# WM_TriacSwitchModuleRev4.net
KiCad netlist of a schematic drawn in EAGLE
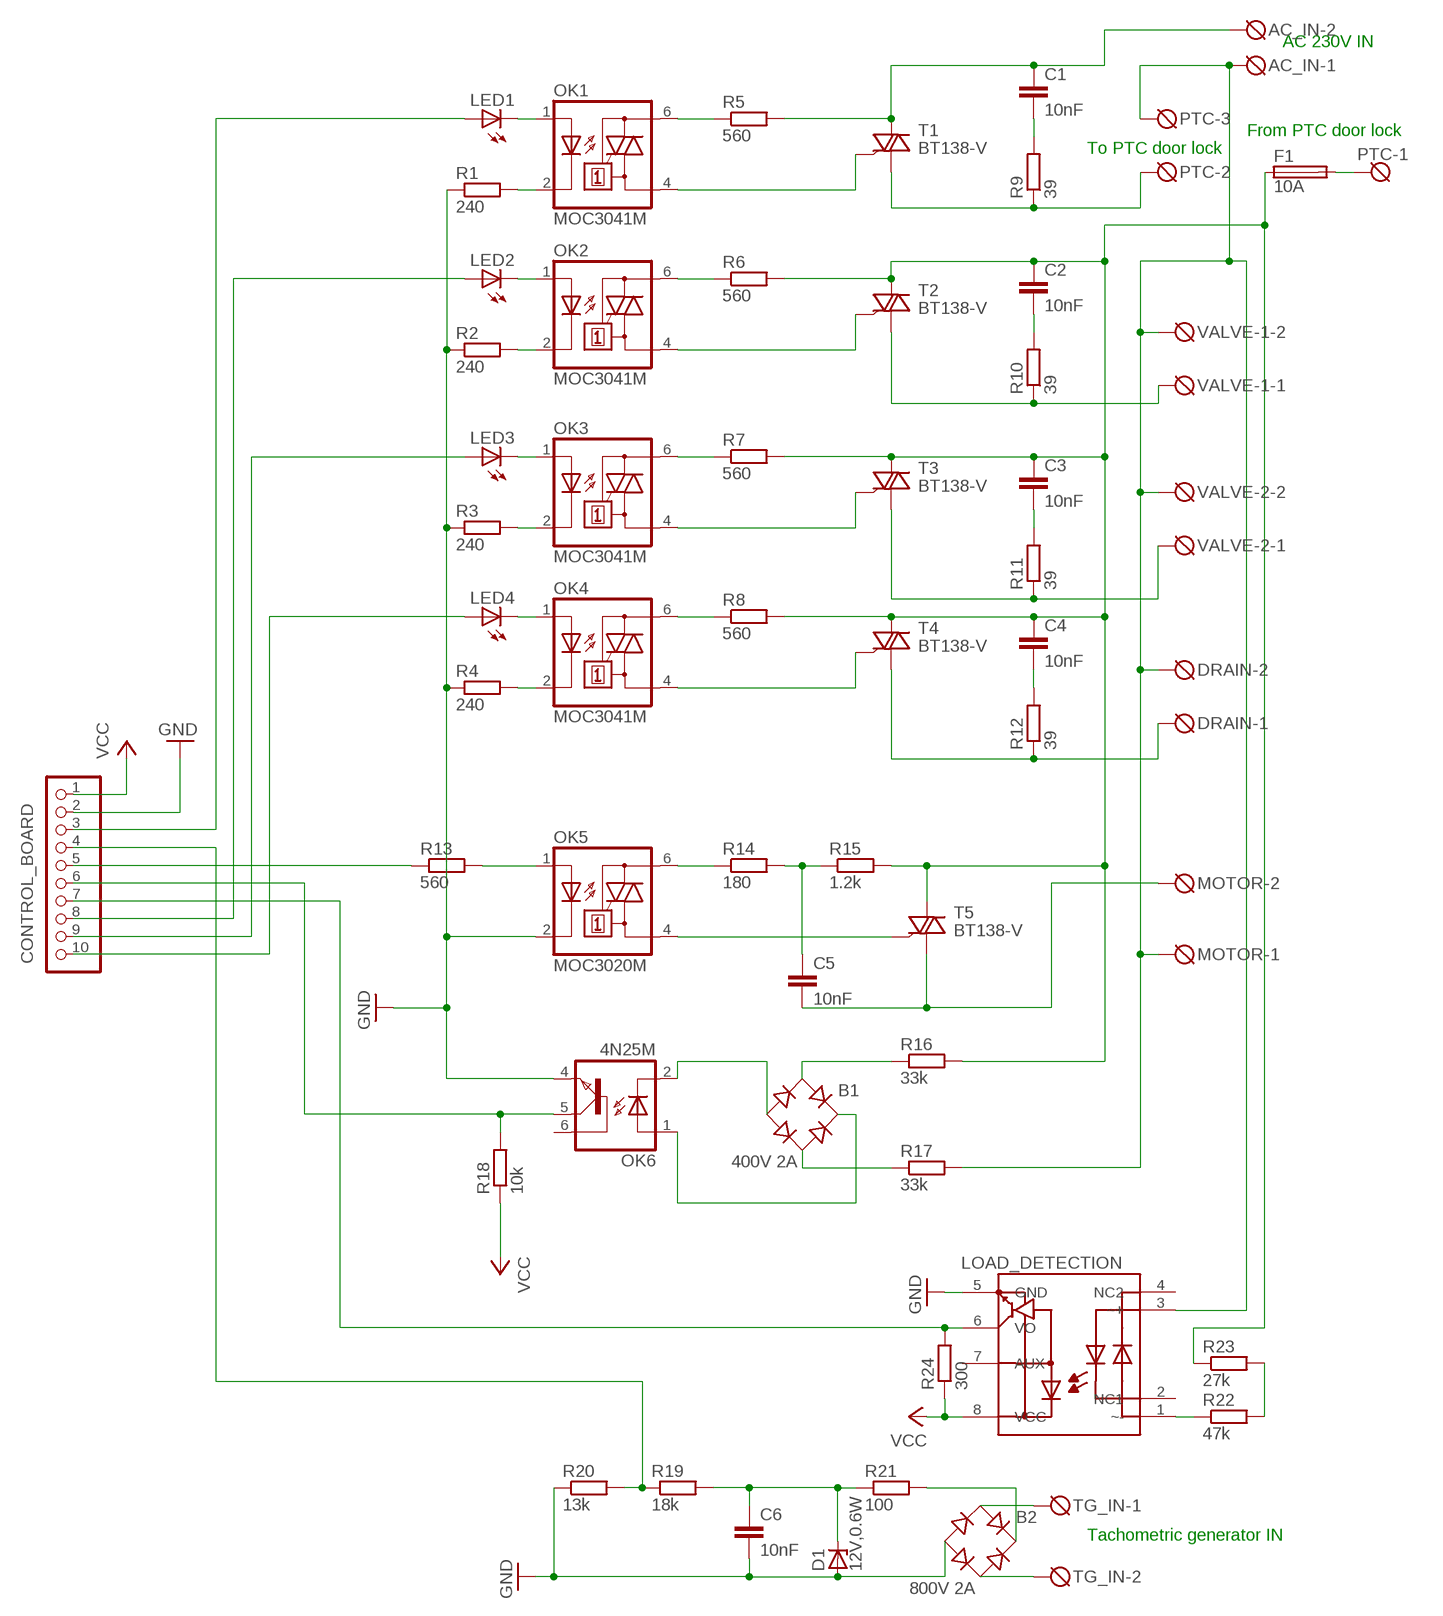
[diagram p0: schematic, sheet 1]

(export (version "E")
  (design (tool "Eeschema 10.0.6"))
  (components
    (comp (ref "AC_IN")
      (value "N L")
      (footprint "eagle-import:DG306-5.0-02P")
      (libsource (lib "eagle-import") (part "DG3XX-02-5.0"))
    )
    (comp (ref "B1")
      (value "400V 2A")
      (footprint "eagle-import:RB1A")
      (libsource (lib "eagle-import") (part "RB1A"))
    )
    (comp (ref "B2")
      (value "800V 2A")
      (footprint "eagle-import:RB1A")
      (libsource (lib "eagle-import") (part "RB1A"))
    )
    (comp (ref "C1")
      (value "10nF")
      (footprint "eagle-import:C150-054X183")
      (libsource (lib "eagle-import") (part "C-EU150-054X183"))
    )
    (comp (ref "C2")
      (value "10nF")
      (footprint "eagle-import:C150-054X183")
      (libsource (lib "eagle-import") (part "C-EU150-054X183"))
    )
    (comp (ref "C3")
      (value "10nF")
      (footprint "eagle-import:C150-054X183")
      (libsource (lib "eagle-import") (part "C-EU150-054X183"))
    )
    (comp (ref "C4")
      (value "10nF")
      (footprint "eagle-import:C150-054X183")
      (libsource (lib "eagle-import") (part "C-EU150-054X183"))
    )
    (comp (ref "C5")
      (value "10nF")
      (footprint "eagle-import:C150-054X183")
      (libsource (lib "eagle-import") (part "C-EU150-054X183"))
    )
    (comp (ref "C6")
      (value "10nF")
      (footprint "eagle-import:C050-024X044")
      (libsource (lib "eagle-import") (part "resistor_C-EU050-024X044"))
    )
    (comp (ref "CONTROL_BOARD")
      (value "PINHD-1X10")
      (footprint "eagle-import:1X10-BIG")
      (libsource (lib "eagle-import") (part "PINHD-1X10"))
    )
    (comp (ref "D1")
      (value "12V,0.6W")
      (footprint "eagle-import:DO35Z10")
      (libsource (lib "eagle-import") (part "ZENER-DIODEDO35Z10"))
    )
    (comp (ref "DRAIN")
      (value "L N")
      (footprint "eagle-import:DG306-5.0-02P")
      (libsource (lib "eagle-import") (part "DG3XX-02-5.0"))
    )
    (comp (ref "F1")
      (value "10A")
      (footprint "eagle-import:SH22,5")
      (libsource (lib "eagle-import") (part "FUSESH22,5"))
    )
    (comp (ref "LED1")
      (value "LEDCHIPLED_1206")
      (footprint "eagle-import:CHIPLED_1206")
      (libsource (lib "eagle-import") (part "LEDCHIPLED_1206"))
    )
    (comp (ref "LED2")
      (value "LEDCHIPLED_1206")
      (footprint "eagle-import:CHIPLED_1206")
      (libsource (lib "eagle-import") (part "LEDCHIPLED_1206"))
    )
    (comp (ref "LED3")
      (value "LEDCHIPLED_1206")
      (footprint "eagle-import:CHIPLED_1206")
      (libsource (lib "eagle-import") (part "LEDCHIPLED_1206"))
    )
    (comp (ref "LED4")
      (value "LEDCHIPLED_1206")
      (footprint "eagle-import:CHIPLED_1206")
      (libsource (lib "eagle-import") (part "LEDCHIPLED_1206"))
    )
    (comp (ref "LOAD_DETECTION")
      (value "MID400")
      (footprint "eagle-import:DIL08")
      (libsource (lib "eagle-import") (part "MID400"))
    )
    (comp (ref "MOTOR")
      (value "N L")
      (footprint "eagle-import:DG306-5.0-02P")
      (libsource (lib "eagle-import") (part "DG3XX-02-5.0"))
    )
    (comp (ref "OK1")
      (value "MOC3041M")
      (footprint "eagle-import:DIL06")
      (fields (field (name "MF") "FAIRCHILD SEMICONDUCTOR"))
      (libsource (lib "eagle-import") (part "MOC3041M"))
    )
    (comp (ref "OK2")
      (value "MOC3041M")
      (footprint "eagle-import:DIL06")
      (fields (field (name "MF") "FAIRCHILD SEMICONDUCTOR"))
      (libsource (lib "eagle-import") (part "MOC3041M"))
    )
    (comp (ref "OK3")
      (value "MOC3041M")
      (footprint "eagle-import:DIL06")
      (fields (field (name "MF") "FAIRCHILD SEMICONDUCTOR"))
      (libsource (lib "eagle-import") (part "MOC3041M"))
    )
    (comp (ref "OK4")
      (value "MOC3041M")
      (footprint "eagle-import:DIL06")
      (fields (field (name "MF") "FAIRCHILD SEMICONDUCTOR"))
      (libsource (lib "eagle-import") (part "MOC3041M"))
    )
    (comp (ref "OK5")
      (value "MOC3020M")
      (footprint "eagle-import:DIL06")
      (fields (field (name "MF") "FAIRCHILD SEMICONDUCTOR") (field (name "MPN") "MOC3020-M"))
      (libsource (lib "eagle-import") (part "MOC30M20"))
    )
    (comp (ref "OK6")
      (value "4N25M")
      (footprint "eagle-import:DIL06")
      (fields (field (name "MPN") "4N25-M"))
      (libsource (lib "eagle-import") (part "4N?M25"))
    )
    (comp (ref "PTC")
      (value "L_IN L_OUT N_OUT")
      (footprint "eagle-import:DG306-5.0-03P")
      (libsource (lib "eagle-import") (part "DG3XX-03-5.0"))
    )
    (comp (ref "R1")
      (value "240")
      (footprint "eagle-import:0207_10")
      (libsource (lib "eagle-import") (part "resistor_R-EU_0207/10"))
    )
    (comp (ref "R2")
      (value "240")
      (footprint "eagle-import:0207_10")
      (libsource (lib "eagle-import") (part "resistor_R-EU_0207/10"))
    )
    (comp (ref "R3")
      (value "240")
      (footprint "eagle-import:0207_10")
      (libsource (lib "eagle-import") (part "resistor_R-EU_0207/10"))
    )
    (comp (ref "R4")
      (value "240")
      (footprint "eagle-import:0207_10")
      (libsource (lib "eagle-import") (part "resistor_R-EU_0207/10"))
    )
    (comp (ref "R5")
      (value "560")
      (footprint "eagle-import:0207_10")
      (libsource (lib "eagle-import") (part "resistor_R-EU_0207/10"))
    )
    (comp (ref "R6")
      (value "560")
      (footprint "eagle-import:0207_10")
      (libsource (lib "eagle-import") (part "resistor_R-EU_0207/10"))
    )
    (comp (ref "R7")
      (value "560")
      (footprint "eagle-import:0207_10")
      (libsource (lib "eagle-import") (part "resistor_R-EU_0207/10"))
    )
    (comp (ref "R8")
      (value "560")
      (footprint "eagle-import:0207_10")
      (libsource (lib "eagle-import") (part "resistor_R-EU_0207/10"))
    )
    (comp (ref "R9")
      (value "39")
      (footprint "eagle-import:0207_10")
      (libsource (lib "eagle-import") (part "resistor_R-EU_0207/10"))
    )
    (comp (ref "R10")
      (value "39")
      (footprint "eagle-import:0207_10")
      (libsource (lib "eagle-import") (part "resistor_R-EU_0207/10"))
    )
    (comp (ref "R11")
      (value "39")
      (footprint "eagle-import:0207_10")
      (libsource (lib "eagle-import") (part "resistor_R-EU_0207/10"))
    )
    (comp (ref "R12")
      (value "39")
      (footprint "eagle-import:0207_10")
      (libsource (lib "eagle-import") (part "resistor_R-EU_0207/10"))
    )
    (comp (ref "R13")
      (value "560")
      (footprint "eagle-import:0207_10")
      (libsource (lib "eagle-import") (part "resistor_R-EU_0207/10"))
    )
    (comp (ref "R14")
      (value "180")
      (footprint "eagle-import:0207_10")
      (libsource (lib "eagle-import") (part "resistor_R-EU_0207/10"))
    )
    (comp (ref "R15")
      (value "1.2k")
      (footprint "eagle-import:0207_10")
      (libsource (lib "eagle-import") (part "resistor_R-EU_0207/10"))
    )
    (comp (ref "R16")
      (value "33k")
      (footprint "eagle-import:0207_10")
      (libsource (lib "eagle-import") (part "resistor_R-EU_0207/10"))
    )
    (comp (ref "R17")
      (value "33k")
      (footprint "eagle-import:0207_10")
      (libsource (lib "eagle-import") (part "resistor_R-EU_0207/10"))
    )
    (comp (ref "R18")
      (value "10k")
      (footprint "eagle-import:0207_10")
      (libsource (lib "eagle-import") (part "resistor_R-EU_0207/10"))
    )
    (comp (ref "R19")
      (value "18k")
      (footprint "eagle-import:0207_10")
      (libsource (lib "eagle-import") (part "resistor_R-EU_0207/10"))
    )
    (comp (ref "R20")
      (value "13k")
      (footprint "eagle-import:0207_10")
      (libsource (lib "eagle-import") (part "resistor_R-EU_0207/10"))
    )
    (comp (ref "R21")
      (value "100")
      (footprint "eagle-import:0207_10")
      (libsource (lib "eagle-import") (part "resistor_R-EU_0207/10"))
    )
    (comp (ref "R22")
      (value "47k")
      (footprint "eagle-import:0207_15")
      (libsource (lib "eagle-import") (part "R-EU_0207/15"))
    )
    (comp (ref "R23")
      (value "27k")
      (footprint "eagle-import:0207_15")
      (libsource (lib "eagle-import") (part "R-EU_0207/15"))
    )
    (comp (ref "R24")
      (value "300")
      (footprint "eagle-import:0207_10")
      (libsource (lib "eagle-import") (part "resistor_R-EU_0207/10"))
    )
    (comp (ref "T1")
      (value "BT138-V")
      (footprint "eagle-import:TO220BV")
      (libsource (lib "eagle-import") (part "BT138-V"))
    )
    (comp (ref "T2")
      (value "BT138-V")
      (footprint "eagle-import:TO220BV")
      (libsource (lib "eagle-import") (part "BT138-V"))
    )
    (comp (ref "T3")
      (value "BT138-V")
      (footprint "eagle-import:TO220BV")
      (libsource (lib "eagle-import") (part "BT138-V"))
    )
    (comp (ref "T4")
      (value "BT138-V")
      (footprint "eagle-import:TO220BV")
      (libsource (lib "eagle-import") (part "BT138-V"))
    )
    (comp (ref "T5")
      (value "BT138-V")
      (footprint "eagle-import:TO220BV")
      (libsource (lib "eagle-import") (part "BT138-V"))
    )
    (comp (ref "TG_IN")
      (value "DG3XX-02-5.0")
      (footprint "eagle-import:DG306-5.0-02P")
      (libsource (lib "eagle-import") (part "DG3XX-02-5.0"))
    )
    (comp (ref "VALVE-1")
      (value "L N")
      (footprint "eagle-import:DG306-5.0-02P")
      (libsource (lib "eagle-import") (part "DG3XX-02-5.0"))
    )
    (comp (ref "VALVE-2")
      (value "L N")
      (footprint "eagle-import:DG306-5.0-02P")
      (libsource (lib "eagle-import") (part "DG3XX-02-5.0"))
    )
  )
  (nets
    (net (code "1") (name "GND") (class "Default")
      (node (ref "B2") (pin "-") (pinfunction "-_-") (pintype "passive"))
      (node (ref "C6") (pin "2") (pinfunction "2_2") (pintype "passive"))
      (node (ref "CONTROL_BOARD") (pin "2") (pinfunction "2_2") (pintype "passive"))
      (node (ref "D1") (pin "A") (pinfunction "A_A") (pintype "passive"))
      (node (ref "LOAD_DETECTION") (pin "5") (pinfunction "GND_5") (pintype "power_in"))
      (node (ref "OK5") (pin "2") (pinfunction "C_2") (pintype "passive"))
      (node (ref "OK6") (pin "4") (pinfunction "EMI_4") (pintype "passive"))
      (node (ref "R1") (pin "1") (pinfunction "1_1") (pintype "passive"))
      (node (ref "R2") (pin "1") (pinfunction "1_1") (pintype "passive"))
      (node (ref "R20") (pin "1") (pinfunction "1_1") (pintype "passive"))
      (node (ref "R3") (pin "1") (pinfunction "1_1") (pintype "passive"))
      (node (ref "R4") (pin "1") (pinfunction "1_1") (pintype "passive"))
    )
    (net (code "2") (name "Net-(AC_INA-KL)") (class "Default")
      (node (ref "AC_IN") (pin "1") (pinfunction "KL_1") (pintype "passive"))
      (node (ref "DRAIN") (pin "2") (pinfunction "KL_2") (pintype "passive"))
      (node (ref "LOAD_DETECTION") (pin "3") (pinfunction "~{+}_3") (pintype "bidirectional"))
      (node (ref "MOTOR") (pin "1") (pinfunction "KL_1") (pintype "passive"))
      (node (ref "PTC") (pin "3") (pinfunction "KL_3") (pintype "passive"))
      (node (ref "R17") (pin "2") (pinfunction "2_2") (pintype "passive"))
      (node (ref "VALVE-1") (pin "2") (pinfunction "KL_2") (pintype "passive"))
      (node (ref "VALVE-2") (pin "2") (pinfunction "KL_2") (pintype "passive"))
    )
    (net (code "3") (name "Net-(AC_INB-KL)") (class "Default")
      (node (ref "AC_IN") (pin "2") (pinfunction "KL_2") (pintype "passive"))
      (node (ref "C1") (pin "1") (pinfunction "1_1") (pintype "passive"))
      (node (ref "R5") (pin "2") (pinfunction "2_2") (pintype "passive"))
      (node (ref "T1") (pin "T2") (pinfunction "A2_T2") (pintype "passive"))
    )
    (net (code "4") (name "Net-(B1-PadAC1)") (class "Default")
      (node (ref "B1") (pin "AC1") (pinfunction "AC1_AC1") (pintype "passive"))
      (node (ref "R16") (pin "1") (pinfunction "1_1") (pintype "passive"))
    )
    (net (code "5") (name "Net-(B1-PadAC2)") (class "Default")
      (node (ref "B1") (pin "AC2") (pinfunction "AC2_AC2") (pintype "passive"))
      (node (ref "R17") (pin "1") (pinfunction "1_1") (pintype "passive"))
    )
    (net (code "6") (name "Net-(B2-Pad+)") (class "Default")
      (node (ref "B2") (pin "+") (pinfunction "+_+") (pintype "passive"))
      (node (ref "R21") (pin "2") (pinfunction "2_2") (pintype "passive"))
    )
    (net (code "7") (name "Net-(C1-Pad2)") (class "Default")
      (node (ref "C1") (pin "2") (pinfunction "2_2") (pintype "passive"))
      (node (ref "R9") (pin "2") (pinfunction "2_2") (pintype "passive"))
    )
    (net (code "8") (name "Net-(C2-Pad2)") (class "Default")
      (node (ref "C2") (pin "2") (pinfunction "2_2") (pintype "passive"))
      (node (ref "R10") (pin "2") (pinfunction "2_2") (pintype "passive"))
    )
    (net (code "9") (name "Net-(C3-Pad2)") (class "Default")
      (node (ref "C3") (pin "2") (pinfunction "2_2") (pintype "passive"))
      (node (ref "R11") (pin "2") (pinfunction "2_2") (pintype "passive"))
    )
    (net (code "10") (name "Net-(C4-Pad2)") (class "Default")
      (node (ref "C4") (pin "2") (pinfunction "2_2") (pintype "passive"))
      (node (ref "R12") (pin "2") (pinfunction "2_2") (pintype "passive"))
    )
    (net (code "11") (name "Net-(C5-Pad1)") (class "Default")
      (node (ref "C5") (pin "1") (pinfunction "1_1") (pintype "passive"))
      (node (ref "R14") (pin "2") (pinfunction "2_2") (pintype "passive"))
      (node (ref "R15") (pin "1") (pinfunction "1_1") (pintype "passive"))
    )
    (net (code "12") (name "Net-(C6-Pad1)") (class "Default")
      (node (ref "C6") (pin "1") (pinfunction "1_1") (pintype "passive"))
      (node (ref "D1") (pin "C") (pinfunction "C_C") (pintype "passive"))
      (node (ref "R19") (pin "2") (pinfunction "2_2") (pintype "passive"))
      (node (ref "R21") (pin "1") (pinfunction "1_1") (pintype "passive"))
    )
    (net (code "13") (name "Net-(CONTROL_BOARD-Pad3)") (class "Default")
      (node (ref "CONTROL_BOARD") (pin "3") (pinfunction "3_3") (pintype "passive"))
      (node (ref "LED1") (pin "A") (pinfunction "A_A") (pintype "passive"))
    )
    (net (code "14") (name "Net-(CONTROL_BOARD-Pad4)") (class "Default")
      (node (ref "CONTROL_BOARD") (pin "4") (pinfunction "4_4") (pintype "passive"))
      (node (ref "R19") (pin "1") (pinfunction "1_1") (pintype "passive"))
      (node (ref "R20") (pin "2") (pinfunction "2_2") (pintype "passive"))
    )
    (net (code "15") (name "Net-(CONTROL_BOARD-Pad5)") (class "Default")
      (node (ref "CONTROL_BOARD") (pin "5") (pinfunction "5_5") (pintype "passive"))
      (node (ref "R13") (pin "1") (pinfunction "1_1") (pintype "passive"))
    )
    (net (code "16") (name "Net-(CONTROL_BOARD-Pad8)") (class "Default")
      (node (ref "CONTROL_BOARD") (pin "8") (pinfunction "8_8") (pintype "passive"))
      (node (ref "LED2") (pin "A") (pinfunction "A_A") (pintype "passive"))
    )
    (net (code "17") (name "Net-(CONTROL_BOARD-Pad9)") (class "Default")
      (node (ref "CONTROL_BOARD") (pin "9") (pinfunction "9_9") (pintype "passive"))
      (node (ref "LED3") (pin "A") (pinfunction "A_A") (pintype "passive"))
    )
    (net (code "18") (name "Net-(CONTROL_BOARD-Pad10)") (class "Default")
      (node (ref "CONTROL_BOARD") (pin "10") (pinfunction "10_10") (pintype "passive"))
      (node (ref "LED4") (pin "A") (pinfunction "A_A") (pintype "passive"))
    )
    (net (code "19") (name "Net-(DRAINA-KL)") (class "Default")
      (node (ref "DRAIN") (pin "1") (pinfunction "KL_1") (pintype "passive"))
      (node (ref "R12") (pin "1") (pinfunction "1_1") (pintype "passive"))
      (node (ref "T4") (pin "T1") (pinfunction "A1_T1") (pintype "passive"))
    )
    (net (code "20") (name "Net-(LOAD_DETECTION-VO)") (class "Default")
      (node (ref "CONTROL_BOARD") (pin "7") (pinfunction "7_7") (pintype "passive"))
      (node (ref "LOAD_DETECTION") (pin "6") (pinfunction "VO_6") (pintype "bidirectional"))
      (node (ref "R24") (pin "2") (pinfunction "2_2") (pintype "passive"))
    )
    (net (code "21") (name "Net-(LOAD_DETECTION-~{-})") (class "Default")
      (node (ref "LOAD_DETECTION") (pin "1") (pinfunction "~{-}_1") (pintype "bidirectional"))
      (node (ref "R22") (pin "1") (pinfunction "1_1") (pintype "passive"))
    )
    (net (code "22") (name "Net-(MOTORB-KL)") (class "Default")
      (node (ref "C5") (pin "2") (pinfunction "2_2") (pintype "passive"))
      (node (ref "MOTOR") (pin "2") (pinfunction "KL_2") (pintype "passive"))
      (node (ref "T5") (pin "T1") (pinfunction "A1_T1") (pintype "passive"))
    )
    (net (code "23") (name "Net-(OK1-A)") (class "Default")
      (node (ref "LED1") (pin "C") (pinfunction "C_C") (pintype "passive"))
      (node (ref "OK1") (pin "1") (pinfunction "A_1") (pintype "passive"))
    )
    (net (code "24") (name "Net-(OK1-A1)") (class "Default")
      (node (ref "OK1") (pin "4") (pinfunction "A1_4") (pintype "passive"))
      (node (ref "T1") (pin "G") (pinfunction "G_G") (pintype "passive"))
    )
    (net (code "25") (name "Net-(OK1-A2)") (class "Default")
      (node (ref "OK1") (pin "6") (pinfunction "A2_6") (pintype "passive"))
      (node (ref "R5") (pin "1") (pinfunction "1_1") (pintype "passive"))
    )
    (net (code "26") (name "Net-(OK1-C)") (class "Default")
      (node (ref "OK1") (pin "2") (pinfunction "C_2") (pintype "passive"))
      (node (ref "R1") (pin "2") (pinfunction "2_2") (pintype "passive"))
    )
    (net (code "27") (name "Net-(OK2-A)") (class "Default")
      (node (ref "LED2") (pin "C") (pinfunction "C_C") (pintype "passive"))
      (node (ref "OK2") (pin "1") (pinfunction "A_1") (pintype "passive"))
    )
    (net (code "28") (name "Net-(OK2-A1)") (class "Default")
      (node (ref "OK2") (pin "4") (pinfunction "A1_4") (pintype "passive"))
      (node (ref "T2") (pin "G") (pinfunction "G_G") (pintype "passive"))
    )
    (net (code "29") (name "Net-(OK2-A2)") (class "Default")
      (node (ref "OK2") (pin "6") (pinfunction "A2_6") (pintype "passive"))
      (node (ref "R6") (pin "1") (pinfunction "1_1") (pintype "passive"))
    )
    (net (code "30") (name "Net-(OK2-C)") (class "Default")
      (node (ref "OK2") (pin "2") (pinfunction "C_2") (pintype "passive"))
      (node (ref "R2") (pin "2") (pinfunction "2_2") (pintype "passive"))
    )
    (net (code "31") (name "Net-(OK3-A)") (class "Default")
      (node (ref "LED3") (pin "C") (pinfunction "C_C") (pintype "passive"))
      (node (ref "OK3") (pin "1") (pinfunction "A_1") (pintype "passive"))
    )
    (net (code "32") (name "Net-(OK3-A1)") (class "Default")
      (node (ref "OK3") (pin "4") (pinfunction "A1_4") (pintype "passive"))
      (node (ref "T3") (pin "G") (pinfunction "G_G") (pintype "passive"))
    )
    (net (code "33") (name "Net-(OK3-A2)") (class "Default")
      (node (ref "OK3") (pin "6") (pinfunction "A2_6") (pintype "passive"))
      (node (ref "R7") (pin "1") (pinfunction "1_1") (pintype "passive"))
    )
    (net (code "34") (name "Net-(OK3-C)") (class "Default")
      (node (ref "OK3") (pin "2") (pinfunction "C_2") (pintype "passive"))
      (node (ref "R3") (pin "2") (pinfunction "2_2") (pintype "passive"))
    )
    (net (code "35") (name "Net-(OK4-A)") (class "Default")
      (node (ref "LED4") (pin "C") (pinfunction "C_C") (pintype "passive"))
      (node (ref "OK4") (pin "1") (pinfunction "A_1") (pintype "passive"))
    )
    (net (code "36") (name "Net-(OK4-A1)") (class "Default")
      (node (ref "OK4") (pin "4") (pinfunction "A1_4") (pintype "passive"))
      (node (ref "T4") (pin "G") (pinfunction "G_G") (pintype "passive"))
    )
    (net (code "37") (name "Net-(OK4-A2)") (class "Default")
      (node (ref "OK4") (pin "6") (pinfunction "A2_6") (pintype "passive"))
      (node (ref "R8") (pin "1") (pinfunction "1_1") (pintype "passive"))
    )
    (net (code "38") (name "Net-(OK4-C)") (class "Default")
      (node (ref "OK4") (pin "2") (pinfunction "C_2") (pintype "passive"))
      (node (ref "R4") (pin "2") (pinfunction "2_2") (pintype "passive"))
    )
    (net (code "39") (name "Net-(OK5-A)") (class "Default")
      (node (ref "OK5") (pin "1") (pinfunction "A_1") (pintype "passive"))
      (node (ref "R13") (pin "2") (pinfunction "2_2") (pintype "passive"))
    )
    (net (code "40") (name "Net-(OK5-A1)") (class "Default")
      (node (ref "OK5") (pin "4") (pinfunction "A1_4") (pintype "passive"))
      (node (ref "T5") (pin "G") (pinfunction "G_G") (pintype "passive"))
    )
    (net (code "41") (name "Net-(OK5-A2)") (class "Default")
      (node (ref "OK5") (pin "6") (pinfunction "A2_6") (pintype "passive"))
      (node (ref "R14") (pin "1") (pinfunction "1_1") (pintype "passive"))
    )
    (net (code "42") (name "Net-(OK6-A)") (class "Default")
      (node (ref "B1") (pin "+") (pinfunction "+_+") (pintype "passive"))
      (node (ref "OK6") (pin "1") (pinfunction "A_1") (pintype "passive"))
    )
    (net (code "43") (name "Net-(OK6-C)") (class "Default")
      (node (ref "B1") (pin "-") (pinfunction "-_-") (pintype "passive"))
      (node (ref "OK6") (pin "2") (pinfunction "C_2") (pintype "passive"))
    )
    (net (code "44") (name "Net-(OK6-COL)") (class "Default")
      (node (ref "CONTROL_BOARD") (pin "6") (pinfunction "6_6") (pintype "passive"))
      (node (ref "OK6") (pin "5") (pinfunction "COL_5") (pintype "passive"))
      (node (ref "R18") (pin "2") (pinfunction "2_2") (pintype "passive"))
    )
    (net (code "45") (name "Net-(PTCA-KL)") (class "Default")
      (node (ref "F1") (pin "2") (pinfunction "2_2") (pintype "passive"))
      (node (ref "PTC") (pin "1") (pinfunction "KL_1") (pintype "passive"))
    )
    (net (code "46") (name "Net-(PTCB-KL)") (class "Default")
      (node (ref "PTC") (pin "2") (pinfunction "KL_2") (pintype "passive"))
      (node (ref "R9") (pin "1") (pinfunction "1_1") (pintype "passive"))
      (node (ref "T1") (pin "T1") (pinfunction "A1_T1") (pintype "passive"))
    )
    (net (code "47") (name "Net-(R22-Pad2)") (class "Default")
      (node (ref "R22") (pin "2") (pinfunction "2_2") (pintype "passive"))
      (node (ref "R23") (pin "2") (pinfunction "2_2") (pintype "passive"))
    )
    (net (code "48") (name "Net-(T2-A1)") (class "Default")
      (node (ref "R10") (pin "1") (pinfunction "1_1") (pintype "passive"))
      (node (ref "T2") (pin "T1") (pinfunction "A1_T1") (pintype "passive"))
      (node (ref "VALVE-1") (pin "1") (pinfunction "KL_1") (pintype "passive"))
    )
    (net (code "49") (name "Net-(T2-A2)") (class "Default")
      (node (ref "C2") (pin "1") (pinfunction "1_1") (pintype "passive"))
      (node (ref "C3") (pin "1") (pinfunction "1_1") (pintype "passive"))
      (node (ref "C4") (pin "1") (pinfunction "1_1") (pintype "passive"))
      (node (ref "F1") (pin "1") (pinfunction "1_1") (pintype "passive"))
      (node (ref "R15") (pin "2") (pinfunction "2_2") (pintype "passive"))
      (node (ref "R16") (pin "2") (pinfunction "2_2") (pintype "passive"))
      (node (ref "R23") (pin "1") (pinfunction "1_1") (pintype "passive"))
      (node (ref "R6") (pin "2") (pinfunction "2_2") (pintype "passive"))
      (node (ref "R7") (pin "2") (pinfunction "2_2") (pintype "passive"))
      (node (ref "R8") (pin "2") (pinfunction "2_2") (pintype "passive"))
      (node (ref "T2") (pin "T2") (pinfunction "A2_T2") (pintype "passive"))
      (node (ref "T3") (pin "T2") (pinfunction "A2_T2") (pintype "passive"))
      (node (ref "T4") (pin "T2") (pinfunction "A2_T2") (pintype "passive"))
      (node (ref "T5") (pin "T2") (pinfunction "A2_T2") (pintype "passive"))
    )
    (net (code "50") (name "Net-(T3-A1)") (class "Default")
      (node (ref "R11") (pin "1") (pinfunction "1_1") (pintype "passive"))
      (node (ref "T3") (pin "T1") (pinfunction "A1_T1") (pintype "passive"))
      (node (ref "VALVE-2") (pin "1") (pinfunction "KL_1") (pintype "passive"))
    )
    (net (code "51") (name "Net-(TG_INA-KL)") (class "Default")
      (node (ref "B2") (pin "AC1") (pinfunction "AC1_AC1") (pintype "passive"))
      (node (ref "TG_IN") (pin "1") (pinfunction "KL_1") (pintype "passive"))
    )
    (net (code "52") (name "Net-(TG_INB-KL)") (class "Default")
      (node (ref "B2") (pin "AC2") (pinfunction "AC2_AC2") (pintype "passive"))
      (node (ref "TG_IN") (pin "2") (pinfunction "KL_2") (pintype "passive"))
    )
    (net (code "53") (name "VCC") (class "Default")
      (node (ref "CONTROL_BOARD") (pin "1") (pinfunction "1_1") (pintype "passive"))
      (node (ref "LOAD_DETECTION") (pin "8") (pinfunction "VCC_8") (pintype "power_in"))
      (node (ref "R18") (pin "1") (pinfunction "1_1") (pintype "passive"))
      (node (ref "R24") (pin "1") (pinfunction "1_1") (pintype "passive"))
    )
    (net (code "54") (name "unconnected-(LOAD_DETECTION-AUX-Pad7)") (class "Default")
      (node (ref "LOAD_DETECTION") (pin "7") (pinfunction "AUX_7") (pintype "bidirectional"))
    )
    (net (code "55") (name "unconnected-(LOAD_DETECTION-NC1-Pad2)") (class "Default")
      (node (ref "LOAD_DETECTION") (pin "2") (pinfunction "NC1_2") (pintype "no_connect"))
    )
    (net (code "56") (name "unconnected-(LOAD_DETECTION-NC2-Pad4)") (class "Default")
      (node (ref "LOAD_DETECTION") (pin "4") (pinfunction "NC2_4") (pintype "no_connect"))
    )
    (net (code "57") (name "unconnected-(OK6-BAS-Pad6)") (class "Default")
      (node (ref "OK6") (pin "6") (pinfunction "BAS_6") (pintype "passive"))
    )
  )
)
